# Library_v50.net
KiCad netlist of a schematic drawn in EAGLE
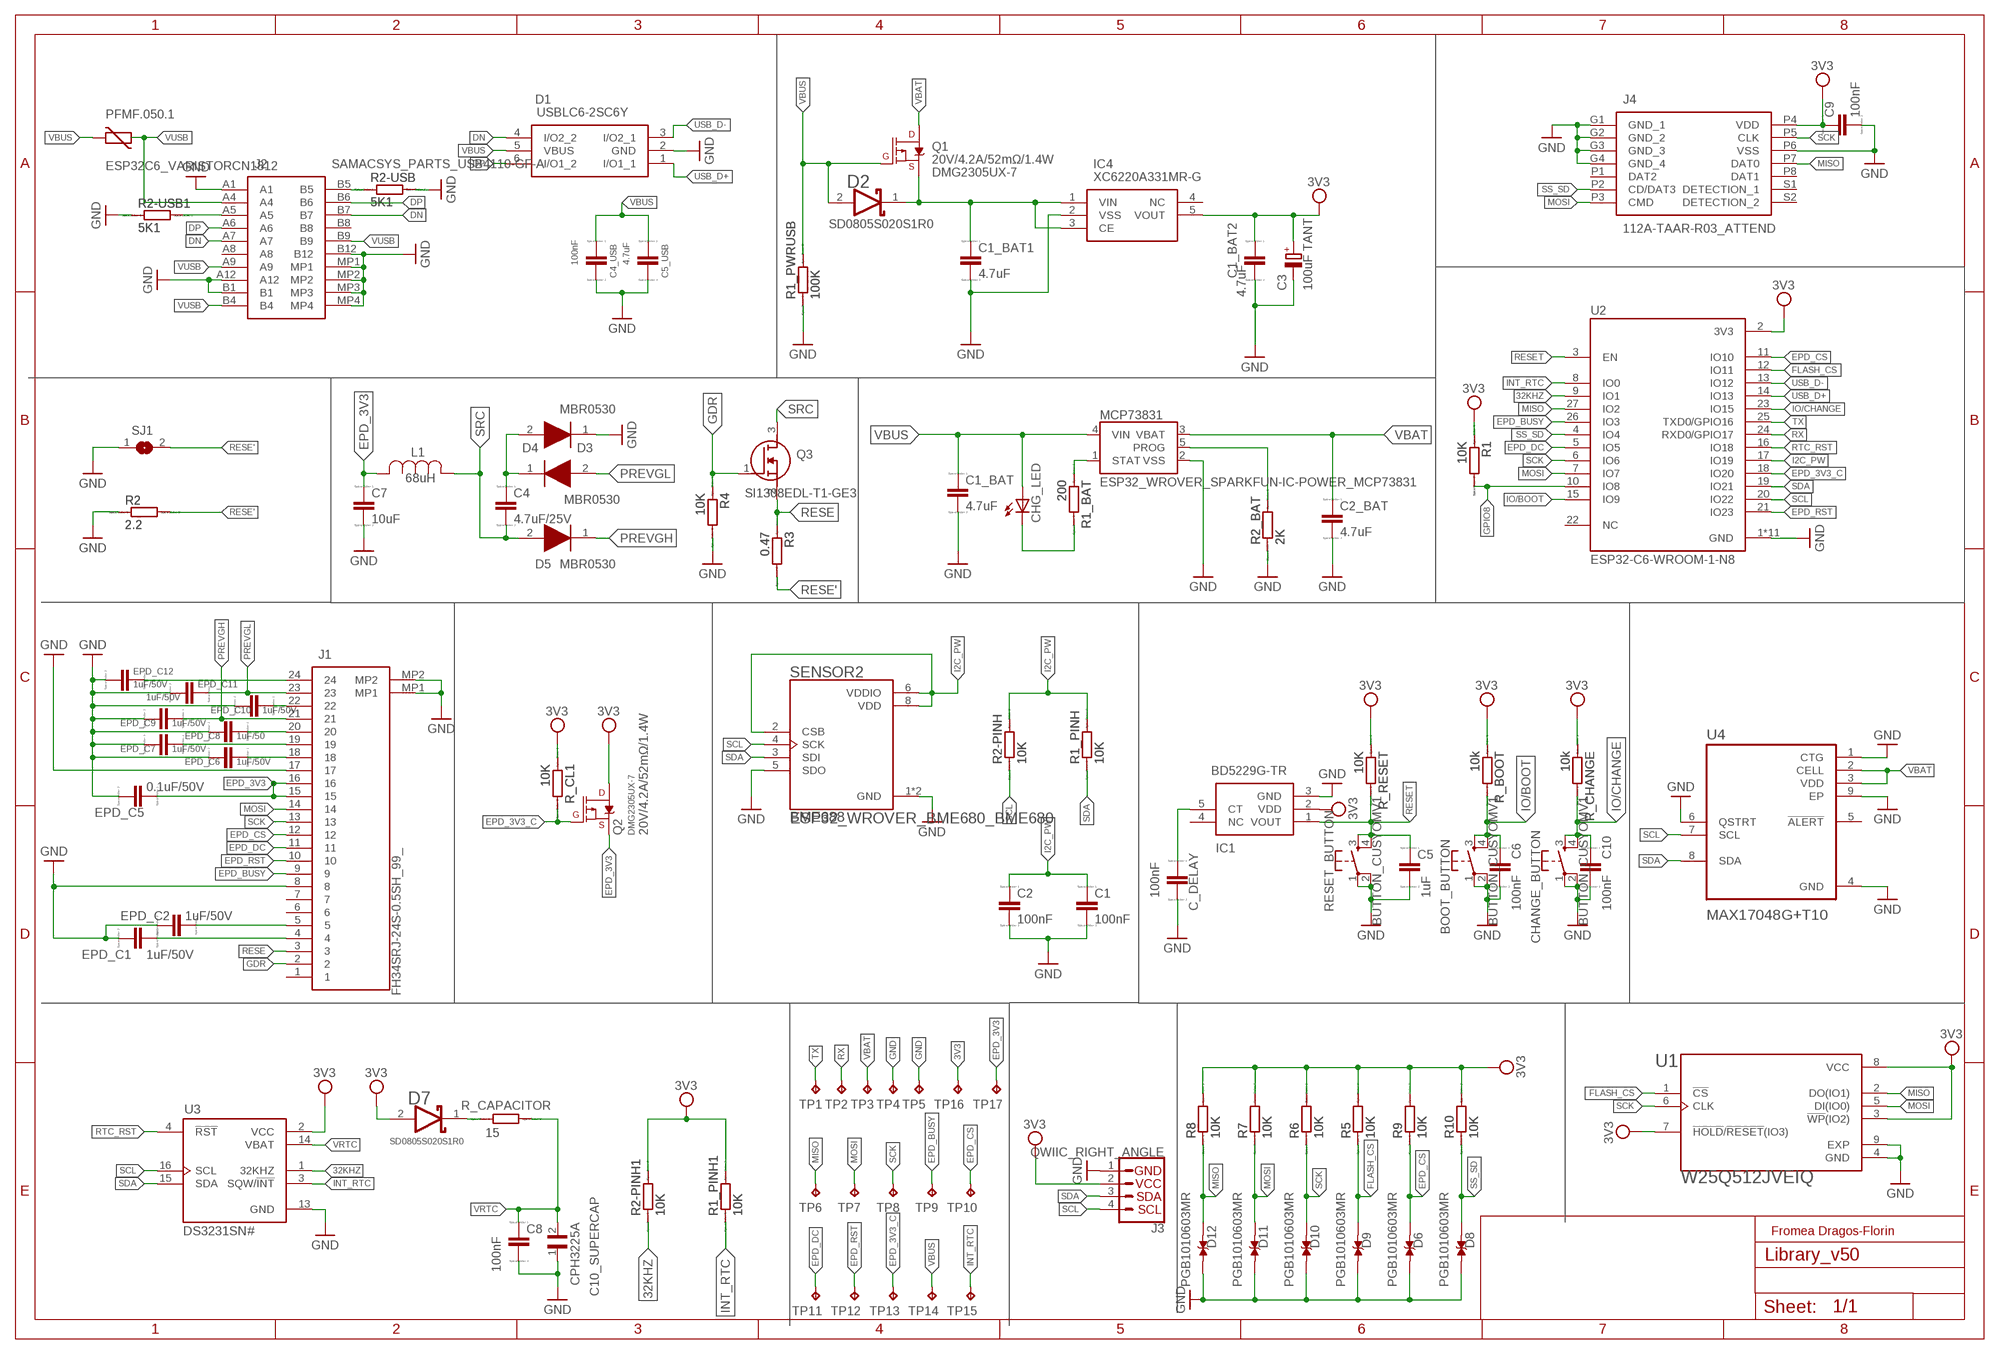
[diagram p0: schematic, sheet 1]

(export (version "E")
  (design (tool "Eeschema 10.0.6"))
  (components
    (comp (ref "BOOT_BUTTON")
      (value "BUTTON_CUSYOMV1")
      (footprint "eagle-import:MYBUTTON")
      (libsource (lib "eagle-import") (part "BUTTON_CUSYOMV1"))
    )
    (comp (ref "C1")
      (value "100nF")
      (footprint "eagle-import:ESP32_WROVER_EAGLE-LTSPICE_C0402")
      (libsource (lib "eagle-import") (part "ESP32_WROVER_EAGLE-LTSPICE_CC0402"))
    )
    (comp (ref "C1_BAT")
      (value "4.7uF")
      (footprint "eagle-import:ESP32_WROVER_EAGLE-LTSPICE_C0402")
      (libsource (lib "eagle-import") (part "ESP32_WROVER_EAGLE-LTSPICE_CC0402"))
    )
    (comp (ref "C1_BAT1")
      (value "4.7uF")
      (footprint "eagle-import:ESP32_WROVER_EAGLE-LTSPICE_C0402")
      (libsource (lib "eagle-import") (part "ESP32_WROVER_EAGLE-LTSPICE_CC0402"))
    )
    (comp (ref "C1_BAT2")
      (value "4.7uF")
      (footprint "eagle-import:ESP32_WROVER_EAGLE-LTSPICE_C0402")
      (libsource (lib "eagle-import") (part "ESP32_WROVER_EAGLE-LTSPICE_CC0402"))
    )
    (comp (ref "C2")
      (value "100nF")
      (footprint "eagle-import:ESP32_WROVER_EAGLE-LTSPICE_C0402")
      (libsource (lib "eagle-import") (part "ESP32_WROVER_EAGLE-LTSPICE_CC0402"))
    )
    (comp (ref "C2_BAT")
      (value "4.7uF")
      (footprint "eagle-import:ESP32_WROVER_EAGLE-LTSPICE_C0402")
      (libsource (lib "eagle-import") (part "ESP32_WROVER_EAGLE-LTSPICE_CC0402"))
    )
    (comp (ref "C3")
      (value "100uF TANT")
      (footprint "eagle-import:RCL_CT3528")
      (libsource (lib "eagle-import") (part "RCL_CPOL-EUCT3528"))
    )
    (comp (ref "C4")
      (value "4.7uF/25V")
      (footprint "eagle-import:ESP32_WROVER_EAGLE-LTSPICE_C0402")
      (libsource (lib "eagle-import") (part "ESP32_WROVER_EAGLE-LTSPICE_CC0402"))
    )
    (comp (ref "C4_USB")
      (value "100nF")
      (footprint "eagle-import:ESP32_WROVER_EAGLE-LTSPICE_C0402")
      (libsource (lib "eagle-import") (part "ESP32_WROVER_EAGLE-LTSPICE_CC0402"))
    )
    (comp (ref "C5")
      (value "1uF")
      (footprint "eagle-import:ESP32_WROVER_EAGLE-LTSPICE_C0402")
      (libsource (lib "eagle-import") (part "ESP32_WROVER_EAGLE-LTSPICE_CC0402"))
    )
    (comp (ref "C5_USB")
      (value "4.7uF")
      (footprint "eagle-import:ESP32_WROVER_EAGLE-LTSPICE_C0402")
      (libsource (lib "eagle-import") (part "ESP32_WROVER_EAGLE-LTSPICE_CC0402"))
    )
    (comp (ref "C6")
      (value "100nF")
      (footprint "eagle-import:ESP32_WROVER_EAGLE-LTSPICE_C0402")
      (libsource (lib "eagle-import") (part "ESP32_WROVER_EAGLE-LTSPICE_CC0402"))
    )
    (comp (ref "C7")
      (value "10uF")
      (footprint "eagle-import:ESP32_WROVER_EAGLE-LTSPICE_C0402")
      (libsource (lib "eagle-import") (part "ESP32_WROVER_EAGLE-LTSPICE_CC0402"))
    )
    (comp (ref "C8")
      (value "100nF")
      (footprint "eagle-import:ESP32_WROVER_EAGLE-LTSPICE_C0402")
      (libsource (lib "eagle-import") (part "ESP32_WROVER_EAGLE-LTSPICE_CC0402"))
    )
    (comp (ref "C9")
      (value "100nF")
      (footprint "eagle-import:ESP32_WROVER_EAGLE-LTSPICE_C0402")
      (libsource (lib "eagle-import") (part "ESP32_WROVER_EAGLE-LTSPICE_CC0402"))
    )
    (comp (ref "C10")
      (value "100nF")
      (footprint "eagle-import:ESP32_WROVER_EAGLE-LTSPICE_C0402")
      (libsource (lib "eagle-import") (part "ESP32_WROVER_EAGLE-LTSPICE_CC0402"))
    )
    (comp (ref "C10_SUPERCAP")
      (value "CPH3225A")
      (footprint "eagle-import:CAPCP3225X100N")
      (fields (field (name "MF") "Seiko Instruments"))
      (libsource (lib "eagle-import") (part "CPH3225A"))
    )
    (comp (ref "CHANGE_BUTTON")
      (value "BUTTON_CUSYOMV1")
      (footprint "eagle-import:MYBUTTON")
      (libsource (lib "eagle-import") (part "BUTTON_CUSYOMV1"))
    )
    (comp (ref "CHG_LED")
      (value "ADAFRUIT_LEDCHIP-LED0603")
      (footprint "eagle-import:ADAFRUIT_CHIP-LED0603")
      (libsource (lib "eagle-import") (part "ADAFRUIT_LEDCHIP-LED0603"))
    )
    (comp (ref "C_DELAY")
      (value "100nF")
      (footprint "eagle-import:ESP32_WROVER_EAGLE-LTSPICE_C0402")
      (libsource (lib "eagle-import") (part "ESP32_WROVER_EAGLE-LTSPICE_CC0402"))
    )
    (comp (ref "D1")
      (value "USBLC6-2SC6Y")
      (footprint "eagle-import:SOT95P280X145-6N")
      (fields (field (name "MF") "STMicroelectronics"))
      (libsource (lib "eagle-import") (part "USBLC6-2SC6Y"))
    )
    (comp (ref "D2")
      (value "ESP32_WROVER_AVX---SD0805S020S1R0_AVX_SD0805S020S1R0_0_0AVX_SD0805S020S1R0_0_0")
      (footprint "eagle-import:ESP32_WROVER_AVX---SD0805S020S1R0_AVX_SD0805S020S1R0_0")
      (fields
        (field (name "DIGIKEY_PART_NUMBER") "478-7800-1-ND")
        (field (name "MF") "AVX")
        (field (name "MOUSER_PART_NUMBER") "581-SD0805S020S1R0")
      )
      (libsource (lib "eagle-import") (part "ESP32_WROVER_AVX---SD0805S020S1R0_AVX_SD0805S020S1R0_0_0AVX_SD0805S020S1R0_0_0"))
    )
    (comp (ref "D3")
      (value "MBR0530")
      (footprint "eagle-import:SOD3716X135N")
      (fields (field (name "MF") "ON Semiconductor"))
      (libsource (lib "eagle-import") (part "MBR0530"))
    )
    (comp (ref "D4")
      (value "MBR0530")
      (footprint "eagle-import:SOD3716X135N")
      (fields (field (name "MF") "ON Semiconductor"))
      (libsource (lib "eagle-import") (part "MBR0530"))
    )
    (comp (ref "D5")
      (value "MBR0530")
      (footprint "eagle-import:SOD3716X135N")
      (fields (field (name "MF") "ON Semiconductor"))
      (libsource (lib "eagle-import") (part "MBR0530"))
    )
    (comp (ref "D6")
      (value "PGB1010603MR")
      (footprint "eagle-import:DIOC1608X36N")
      (fields (field (name "MF") "Littelfuse Inc."))
      (libsource (lib "eagle-import") (part "PGB1010603MR"))
    )
    (comp (ref "D7")
      (value "ESP32_WROVER_AVX---SD0805S020S1R0_AVX_SD0805S020S1R0_0_0AVX_SD0805S020S1R0_0_0")
      (footprint "eagle-import:ESP32_WROVER_AVX---SD0805S020S1R0_AVX_SD0805S020S1R0_0")
      (fields
        (field (name "DIGIKEY_PART_NUMBER") "478-7800-1-ND")
        (field (name "MF") "AVX")
        (field (name "MOUSER_PART_NUMBER") "581-SD0805S020S1R0")
      )
      (libsource (lib "eagle-import") (part "ESP32_WROVER_AVX---SD0805S020S1R0_AVX_SD0805S020S1R0_0_0AVX_SD0805S020S1R0_0_0"))
    )
    (comp (ref "D8")
      (value "PGB1010603MR")
      (footprint "eagle-import:DIOC1608X36N")
      (fields (field (name "MF") "Littelfuse Inc."))
      (libsource (lib "eagle-import") (part "PGB1010603MR"))
    )
    (comp (ref "D9")
      (value "PGB1010603MR")
      (footprint "eagle-import:DIOC1608X36N")
      (fields (field (name "MF") "Littelfuse Inc."))
      (libsource (lib "eagle-import") (part "PGB1010603MR"))
    )
    (comp (ref "D10")
      (value "PGB1010603MR")
      (footprint "eagle-import:DIOC1608X36N")
      (fields (field (name "MF") "Littelfuse Inc."))
      (libsource (lib "eagle-import") (part "PGB1010603MR"))
    )
    (comp (ref "D11")
      (value "PGB1010603MR")
      (footprint "eagle-import:DIOC1608X36N")
      (fields (field (name "MF") "Littelfuse Inc."))
      (libsource (lib "eagle-import") (part "PGB1010603MR"))
    )
    (comp (ref "D12")
      (value "PGB1010603MR")
      (footprint "eagle-import:DIOC1608X36N")
      (fields (field (name "MF") "Littelfuse Inc."))
      (libsource (lib "eagle-import") (part "PGB1010603MR"))
    )
    (comp (ref "EPD_C1")
      (value "1uF/50V")
      (footprint "eagle-import:ESP32_WROVER_EAGLE-LTSPICE_C0402")
      (libsource (lib "eagle-import") (part "ESP32_WROVER_EAGLE-LTSPICE_CC0402"))
    )
    (comp (ref "EPD_C2")
      (value "1uF/50V")
      (footprint "eagle-import:ESP32_WROVER_EAGLE-LTSPICE_C0402")
      (libsource (lib "eagle-import") (part "ESP32_WROVER_EAGLE-LTSPICE_CC0402"))
    )
    (comp (ref "EPD_C5")
      (value "0.1uF/50V")
      (footprint "eagle-import:ESP32_WROVER_EAGLE-LTSPICE_C0402")
      (libsource (lib "eagle-import") (part "ESP32_WROVER_EAGLE-LTSPICE_CC0402"))
    )
    (comp (ref "EPD_C6")
      (value "1uF/50V")
      (footprint "eagle-import:ESP32_WROVER_EAGLE-LTSPICE_C0402")
      (libsource (lib "eagle-import") (part "ESP32_WROVER_EAGLE-LTSPICE_CC0402"))
    )
    (comp (ref "EPD_C7")
      (value "1uF/50V")
      (footprint "eagle-import:ESP32_WROVER_EAGLE-LTSPICE_C0402")
      (libsource (lib "eagle-import") (part "ESP32_WROVER_EAGLE-LTSPICE_CC0402"))
    )
    (comp (ref "EPD_C8")
      (value "1uF/50")
      (footprint "eagle-import:ESP32_WROVER_EAGLE-LTSPICE_C0402")
      (libsource (lib "eagle-import") (part "ESP32_WROVER_EAGLE-LTSPICE_CC0402"))
    )
    (comp (ref "EPD_C9")
      (value "1uF/50V")
      (footprint "eagle-import:ESP32_WROVER_EAGLE-LTSPICE_C0402")
      (libsource (lib "eagle-import") (part "ESP32_WROVER_EAGLE-LTSPICE_CC0402"))
    )
    (comp (ref "EPD_C10")
      (value "1uF/50V")
      (footprint "eagle-import:ESP32_WROVER_EAGLE-LTSPICE_C0402")
      (libsource (lib "eagle-import") (part "ESP32_WROVER_EAGLE-LTSPICE_CC0402"))
    )
    (comp (ref "EPD_C11")
      (value "1uF/50V")
      (footprint "eagle-import:ESP32_WROVER_EAGLE-LTSPICE_C0402")
      (libsource (lib "eagle-import") (part "ESP32_WROVER_EAGLE-LTSPICE_CC0402"))
    )
    (comp (ref "EPD_C12")
      (value "1uF/50V")
      (footprint "eagle-import:ESP32_WROVER_EAGLE-LTSPICE_C0402")
      (libsource (lib "eagle-import") (part "ESP32_WROVER_EAGLE-LTSPICE_CC0402"))
    )
    (comp (ref "IC1")
      (value "BD5229G-TR")
      (footprint "eagle-import:SOT95P280X125-5N")
      (fields (field (name "MOUSER_PART_NUMBER") "755-BD5229G-TR"))
      (libsource (lib "eagle-import") (part "BD5229G-TR"))
    )
    (comp (ref "IC4")
      (value "XC6220A331MR-G")
      (footprint "eagle-import:SOT95P280X120-5N")
      (fields (field (name "MOUSER_PART_NUMBER") "865-XC6220A331MR-G"))
      (libsource (lib "eagle-import") (part "XC6220A331MR-G"))
    )
    (comp (ref "J1")
      (value "FH34SRJ-24S-0.5SH_99_")
      (footprint "eagle-import:FH34SRJ24S05SH99")
      (fields
        (field (name "MANUFACTURER_PART_NUMBER") "FH34SRJ-24S-0.5SH(99)")
        (field (name "MOUSER_PART_NUMBER") "798-FH34SRJ24S05SH99")
      )
      (libsource (lib "eagle-import") (part "FH34SRJ-24S-0.5SH_99_"))
    )
    (comp (ref "J2")
      (value "SAMACSYS_PARTS_USB4110-GF-A")
      (footprint "eagle-import:SAMACSYS_PARTS_USB4110GFA")
      (fields
        (field (name "MANUFACTURER_PART_NUMBER") "USB4110-GF-A")
        (field (name "MOUSER_PART_NUMBER") "640-USB4110-GF-A")
      )
      (libsource (lib "eagle-import") (part "SAMACSYS_PARTS_USB4110-GF-A"))
    )
    (comp (ref "J3")
      (value "QWIIC_RIGHT_ANGLE")
      (footprint "eagle-import:JST04_1MM_RA")
      (libsource (lib "eagle-import") (part "QWIIC_CONNECTORJS-1MM"))
    )
    (comp (ref "J4")
      (value "112A-TAAR-R03_ATTEND")
      (footprint "eagle-import:112ATAARR03ATTEND")
      (fields (field (name "MANUFACTURER_PART_NUMBER") "112A-TAAR-R03 ATTEND"))
      (libsource (lib "eagle-import") (part "112A-TAAR-R03_ATTEND"))
    )
    (comp (ref "L1")
      (value "68uH")
      (footprint "eagle-import:IND_4828-WE-TPC_WRE")
      (fields
        (field (name "MANUFACTURER_PART_NUMBER") "744043680")
        (field (name "COPYRIGHT") "Copyright (C) 2024 Ultra Librarian. All rights reserved.")
      )
      (libsource (lib "eagle-import") (part "744043680IND_4828-WE-TPC_WRE"))
    )
    (comp (ref "MCP73831")
      (value "ESP32_WROVER_SPARKFUN-IC-POWER_MCP73831")
      (footprint "eagle-import:ESP32_WROVER_SPARKFUN-IC-POWER_SOT23-5")
      (libsource (lib "eagle-import") (part "ESP32_WROVER_SPARKFUN-IC-POWER_MCP73831"))
    )
    (comp (ref "PFMF.050.1")
      (value "ESP32C6_VARISTORCN1812")
      (footprint "eagle-import:ESP32C6_VARISTOR_CT_CN1812")
      (libsource (lib "eagle-import") (part "ESP32C6_VARISTORCN1812"))
    )
    (comp (ref "Q1")
      (value "20V/4.2A/52mΩ/1.4W")
      (footprint "eagle-import:ESP32_WROVER_SPARKFUN-DISCRETESEMI_SOT23-3")
      (libsource (lib "eagle-import") (part "ESP32_WROVER_SPARKFUN-DISCRETESEMI_MOSFET_PCH-DMG2305UX-7"))
    )
    (comp (ref "Q2")
      (value "20V/4.2A/52mΩ/1.4W")
      (footprint "eagle-import:ESP32_WROVER_SPARKFUN-DISCRETESEMI_SOT23-3")
      (libsource (lib "eagle-import") (part "ESP32_WROVER_SPARKFUN-DISCRETESEMI_MOSFET_PCH-DMG2305UX-7"))
    )
    (comp (ref "Q3")
      (value "SI1308EDL-T1-GE3")
      (footprint "eagle-import:SOT65P210X110-3N")
      (fields (field (name "MF") "Vishay Siliconix"))
      (libsource (lib "eagle-import") (part "SI1308EDL-T1-GE3"))
    )
    (comp (ref "R1")
      (value "10K")
      (footprint "eagle-import:ESP32_WROVER_EAGLE-LTSPICE_R0402")
      (libsource (lib "eagle-import") (part "ESP32_WROVER_EAGLE-LTSPICE_RR0402"))
    )
    (comp (ref "R1_BAT")
      (value "200")
      (footprint "eagle-import:ESP32_WROVER_EAGLE-LTSPICE_R0402")
      (libsource (lib "eagle-import") (part "ESP32_WROVER_EAGLE-LTSPICE_RR0402"))
    )
    (comp (ref "R1_PINH")
      (value "10K")
      (footprint "eagle-import:ESP32_WROVER_EAGLE-LTSPICE_R0402")
      (libsource (lib "eagle-import") (part "ESP32_WROVER_EAGLE-LTSPICE_RR0402"))
    )
    (comp (ref "R1_PINH1")
      (value "10K")
      (footprint "eagle-import:ESP32_WROVER_EAGLE-LTSPICE_R0402")
      (libsource (lib "eagle-import") (part "ESP32_WROVER_EAGLE-LTSPICE_RR0402"))
    )
    (comp (ref "R1_PWRUSB")
      (value "100K")
      (footprint "eagle-import:ESP32_WROVER_EAGLE-LTSPICE_R0402")
      (libsource (lib "eagle-import") (part "ESP32_WROVER_EAGLE-LTSPICE_RR0402"))
    )
    (comp (ref "R2")
      (value "2.2")
      (footprint "eagle-import:ESP32_WROVER_EAGLE-LTSPICE_R0402")
      (libsource (lib "eagle-import") (part "ESP32_WROVER_EAGLE-LTSPICE_RR0402"))
    )
    (comp (ref "R2-PINH")
      (value "10K")
      (footprint "eagle-import:ESP32_WROVER_EAGLE-LTSPICE_R0402")
      (libsource (lib "eagle-import") (part "ESP32_WROVER_EAGLE-LTSPICE_RR0402"))
    )
    (comp (ref "R2-PINH1")
      (value "10K")
      (footprint "eagle-import:ESP32_WROVER_EAGLE-LTSPICE_R0402")
      (libsource (lib "eagle-import") (part "ESP32_WROVER_EAGLE-LTSPICE_RR0402"))
    )
    (comp (ref "R2-USB")
      (value "5K1")
      (footprint "eagle-import:ESP32_WROVER_EAGLE-LTSPICE_R0402")
      (libsource (lib "eagle-import") (part "ESP32_WROVER_EAGLE-LTSPICE_RR0402"))
    )
    (comp (ref "R2-USB1")
      (value "5K1")
      (footprint "eagle-import:ESP32_WROVER_EAGLE-LTSPICE_R0402")
      (libsource (lib "eagle-import") (part "ESP32_WROVER_EAGLE-LTSPICE_RR0402"))
    )
    (comp (ref "R2_BAT")
      (value "2K")
      (footprint "eagle-import:ESP32_WROVER_EAGLE-LTSPICE_R0402")
      (libsource (lib "eagle-import") (part "ESP32_WROVER_EAGLE-LTSPICE_RR0402"))
    )
    (comp (ref "R3")
      (value "0.47")
      (footprint "eagle-import:ESP32_WROVER_EAGLE-LTSPICE_R0402")
      (libsource (lib "eagle-import") (part "ESP32_WROVER_EAGLE-LTSPICE_RR0402"))
    )
    (comp (ref "R4")
      (value "10K")
      (footprint "eagle-import:ESP32_WROVER_EAGLE-LTSPICE_R0402")
      (libsource (lib "eagle-import") (part "ESP32_WROVER_EAGLE-LTSPICE_RR0402"))
    )
    (comp (ref "R5")
      (value "10K")
      (footprint "eagle-import:ESP32_WROVER_EAGLE-LTSPICE_R0402")
      (libsource (lib "eagle-import") (part "ESP32_WROVER_EAGLE-LTSPICE_RR0402"))
    )
    (comp (ref "R6")
      (value "10K")
      (footprint "eagle-import:ESP32_WROVER_EAGLE-LTSPICE_R0402")
      (libsource (lib "eagle-import") (part "ESP32_WROVER_EAGLE-LTSPICE_RR0402"))
    )
    (comp (ref "R7")
      (value "10K")
      (footprint "eagle-import:ESP32_WROVER_EAGLE-LTSPICE_R0402")
      (libsource (lib "eagle-import") (part "ESP32_WROVER_EAGLE-LTSPICE_RR0402"))
    )
    (comp (ref "R8")
      (value "10K")
      (footprint "eagle-import:ESP32_WROVER_EAGLE-LTSPICE_R0402")
      (libsource (lib "eagle-import") (part "ESP32_WROVER_EAGLE-LTSPICE_RR0402"))
    )
    (comp (ref "R9")
      (value "10K")
      (footprint "eagle-import:ESP32_WROVER_EAGLE-LTSPICE_R0402")
      (libsource (lib "eagle-import") (part "ESP32_WROVER_EAGLE-LTSPICE_RR0402"))
    )
    (comp (ref "R10")
      (value "10K")
      (footprint "eagle-import:ESP32_WROVER_EAGLE-LTSPICE_R0402")
      (libsource (lib "eagle-import") (part "ESP32_WROVER_EAGLE-LTSPICE_RR0402"))
    )
    (comp (ref "RESET_BUTTON")
      (value "BUTTON_CUSYOMV1")
      (footprint "eagle-import:MYBUTTON")
      (libsource (lib "eagle-import") (part "BUTTON_CUSYOMV1"))
    )
    (comp (ref "R_BOOT")
      (value "10k")
      (footprint "eagle-import:ESP32_WROVER_EAGLE-LTSPICE_R0402")
      (libsource (lib "eagle-import") (part "ESP32_WROVER_EAGLE-LTSPICE_RR0402"))
    )
    (comp (ref "R_CAPACITOR")
      (value "15")
      (footprint "eagle-import:ESP32_WROVER_EAGLE-LTSPICE_R0402")
      (libsource (lib "eagle-import") (part "ESP32_WROVER_EAGLE-LTSPICE_RR0402"))
    )
    (comp (ref "R_CHANGE")
      (value "10k")
      (footprint "eagle-import:ESP32_WROVER_EAGLE-LTSPICE_R0402")
      (libsource (lib "eagle-import") (part "ESP32_WROVER_EAGLE-LTSPICE_RR0402"))
    )
    (comp (ref "R_CL1")
      (value "10K")
      (footprint "eagle-import:ESP32_WROVER_EAGLE-LTSPICE_R0402")
      (libsource (lib "eagle-import") (part "ESP32_WROVER_EAGLE-LTSPICE_RR0402"))
    )
    (comp (ref "R_RESET")
      (value "10K")
      (footprint "eagle-import:ESP32_WROVER_EAGLE-LTSPICE_R0402")
      (libsource (lib "eagle-import") (part "ESP32_WROVER_EAGLE-LTSPICE_RR0402"))
    )
    (comp (ref "SENSOR2")
      (value "ESP32_WROVER_BME680_BME680")
      (footprint "eagle-import:ESP32_WROVER_BME680_PSON80P300X300X100-8N")
      (fields (field (name "MF") "Bosch Sensortec") (field (name "MP") "BME680"))
      (libsource (lib "eagle-import") (part "ESP32_WROVER_BME680_BME680"))
    )
    (comp (ref "SJ1") (value "SJ") (footprint "eagle-import:SJ") (libsource (lib "eagle-import") (part "SJ")))
    (comp (ref "TP1")
      (value "TPTP20R")
      (footprint "eagle-import:TP20R")
      (libsource (lib "eagle-import") (part "TPTP20R"))
    )
    (comp (ref "TP2")
      (value "TPTP20R")
      (footprint "eagle-import:TP20R")
      (libsource (lib "eagle-import") (part "TPTP20R"))
    )
    (comp (ref "TP3")
      (value "TPTP20R")
      (footprint "eagle-import:TP20R")
      (libsource (lib "eagle-import") (part "TPTP20R"))
    )
    (comp (ref "TP4")
      (value "TPTP20R")
      (footprint "eagle-import:TP20R")
      (libsource (lib "eagle-import") (part "TPTP20R"))
    )
    (comp (ref "TP5")
      (value "TPTP20R")
      (footprint "eagle-import:TP20R")
      (libsource (lib "eagle-import") (part "TPTP20R"))
    )
    (comp (ref "TP6")
      (value "TPTP20R")
      (footprint "eagle-import:TP20R")
      (libsource (lib "eagle-import") (part "TPTP20R"))
    )
    (comp (ref "TP7")
      (value "TPTP20R")
      (footprint "eagle-import:TP20R")
      (libsource (lib "eagle-import") (part "TPTP20R"))
    )
    (comp (ref "TP8")
      (value "TPTP20R")
      (footprint "eagle-import:TP20R")
      (libsource (lib "eagle-import") (part "TPTP20R"))
    )
    (comp (ref "TP9")
      (value "TPTP20R")
      (footprint "eagle-import:TP20R")
      (libsource (lib "eagle-import") (part "TPTP20R"))
    )
    (comp (ref "TP10")
      (value "TPTP20R")
      (footprint "eagle-import:TP20R")
      (libsource (lib "eagle-import") (part "TPTP20R"))
    )
    (comp (ref "TP11")
      (value "TPTP20R")
      (footprint "eagle-import:TP20R")
      (libsource (lib "eagle-import") (part "TPTP20R"))
    )
    (comp (ref "TP12")
      (value "TPTP20R")
      (footprint "eagle-import:TP20R")
      (libsource (lib "eagle-import") (part "TPTP20R"))
    )
    (comp (ref "TP13")
      (value "TPTP20R")
      (footprint "eagle-import:TP20R")
      (libsource (lib "eagle-import") (part "TPTP20R"))
    )
    (comp (ref "TP14")
      (value "TPTP20R")
      (footprint "eagle-import:TP20R")
      (libsource (lib "eagle-import") (part "TPTP20R"))
    )
    (comp (ref "TP15")
      (value "TPTP20R")
      (footprint "eagle-import:TP20R")
      (libsource (lib "eagle-import") (part "TPTP20R"))
    )
    (comp (ref "TP16")
      (value "TPTP20R")
      (footprint "eagle-import:TP20R")
      (libsource (lib "eagle-import") (part "TPTP20R"))
    )
    (comp (ref "TP17")
      (value "TPTP20R")
      (footprint "eagle-import:TP20R")
      (libsource (lib "eagle-import") (part "TPTP20R"))
    )
    (comp (ref "U1")
      (value "W25Q512JVEIQ")
      (footprint "eagle-import:SON127P600X800X80-9N")
      (fields (field (name "MF") "Winbond Electronics"))
      (libsource (lib "eagle-import") (part "W25Q512JVEIQ"))
    )
    (comp (ref "U2")
      (value "ESP32-C6-WROOM-1-N8")
      (footprint "eagle-import:XCVR_ESP32-C6-WROOM-1-N8")
      (fields (field (name "MF") "Espressif Systems"))
      (libsource (lib "eagle-import") (part "ESP32-C6-WROOM-1-N8"))
    )
    (comp (ref "U3")
      (value "DS3231SN#")
      (footprint "eagle-import:SOIC127P1032X265-16N")
      (fields (field (name "MF") "Analog Devices"))
      (libsource (lib "eagle-import") (part "DS3231SN#"))
    )
    (comp (ref "U4")
      (value "MAX17048G+T10")
      (footprint "eagle-import:SON50P200X200X80-9N")
      (fields (field (name "MF") "Analog Devices"))
      (libsource (lib "eagle-import") (part "MAX17048G+T10"))
    )
  )
  (nets
    (net (code "1") (name "3V3") (class "Default")
      (node (ref "C1_BAT2") (pin "1") (pinfunction "1_1") (pintype "passive"))
      (node (ref "C3") (pin "+") (pinfunction "+_+") (pintype "passive"))
      (node (ref "C9") (pin "1") (pinfunction "1_1") (pintype "passive"))
      (node (ref "D7") (pin "2") (pinfunction "ANODE_2") (pintype "bidirectional"))
      (node (ref "IC1") (pin "2") (pinfunction "VDD_2") (pintype "bidirectional"))
      (node (ref "IC4") (pin "5") (pinfunction "VOUT_5") (pintype "bidirectional"))
      (node (ref "J3") (pin "2") (pinfunction "2_2") (pintype "power_in"))
      (node (ref "J4") (pin "P4") (pinfunction "VDD_P4") (pintype "bidirectional"))
      (node (ref "Q2") (pin "3") (pinfunction "D_3") (pintype "bidirectional"))
      (node (ref "R1") (pin "1") (pinfunction "1_1") (pintype "passive"))
      (node (ref "R10") (pin "2") (pinfunction "2_2") (pintype "passive"))
      (node (ref "R1_PINH1") (pin "2") (pinfunction "2_2") (pintype "passive"))
      (node (ref "R2-PINH1") (pin "2") (pinfunction "2_2") (pintype "passive"))
      (node (ref "R5") (pin "2") (pinfunction "2_2") (pintype "passive"))
      (node (ref "R6") (pin "2") (pinfunction "2_2") (pintype "passive"))
      (node (ref "R7") (pin "2") (pinfunction "2_2") (pintype "passive"))
      (node (ref "R8") (pin "2") (pinfunction "2_2") (pintype "passive"))
      (node (ref "R9") (pin "2") (pinfunction "2_2") (pintype "passive"))
      (node (ref "R_BOOT") (pin "1") (pinfunction "1_1") (pintype "passive"))
      (node (ref "R_CHANGE") (pin "1") (pinfunction "1_1") (pintype "passive"))
      (node (ref "R_CL1") (pin "1") (pinfunction "1_1") (pintype "passive"))
      (node (ref "R_RESET") (pin "1") (pinfunction "1_1") (pintype "passive"))
      (node (ref "TP16") (pin "TP") (pinfunction "TP_TP") (pintype "input"))
      (node (ref "U1") (pin "3") (pinfunction "~{WP}(IO2)_3") (pintype "bidirectional"))
      (node (ref "U1") (pin "7") (pinfunction "~{HOLD}/~{RESET}(IO3)_7") (pintype "bidirectional"))
      (node (ref "U1") (pin "8") (pinfunction "VCC_8") (pintype "power_in"))
      (node (ref "U2") (pin "2") (pinfunction "3V3_2") (pintype "power_in"))
      (node (ref "U3") (pin "2") (pinfunction "VCC_2") (pintype "power_in"))
    )
    (net (code "2") (name "32KHZ") (class "Default")
      (node (ref "R2-PINH1") (pin "1") (pinfunction "1_1") (pintype "passive"))
      (node (ref "U2") (pin "9") (pinfunction "IO1_9") (pintype "bidirectional"))
      (node (ref "U3") (pin "1") (pinfunction "32KHZ_1") (pintype "output"))
    )
    (net (code "3") (name "DN") (class "Default")
      (node (ref "D1") (pin "4") (pinfunction "I/O2_2_4") (pintype "bidirectional"))
      (node (ref "J2") (pin "A7") (pinfunction "A7_A7") (pintype "bidirectional"))
      (node (ref "J2") (pin "B7") (pinfunction "B7_B7") (pintype "bidirectional"))
    )
    (net (code "4") (name "DP") (class "Default")
      (node (ref "D1") (pin "6") (pinfunction "I/O1_2_6") (pintype "bidirectional"))
      (node (ref "J2") (pin "A6") (pinfunction "A6_A6") (pintype "bidirectional"))
      (node (ref "J2") (pin "B6") (pinfunction "B6_B6") (pintype "bidirectional"))
    )
    (net (code "5") (name "EPD_3V3") (class "Default")
      (node (ref "C7") (pin "1") (pinfunction "1_1") (pintype "passive"))
      (node (ref "EPD_C5") (pin "1") (pinfunction "1_1") (pintype "passive"))
      (node (ref "J1") (pin "15") (pinfunction "15_15") (pintype "bidirectional"))
      (node (ref "J1") (pin "16") (pinfunction "16_16") (pintype "bidirectional"))
      (node (ref "L1") (pin "2") (pinfunction "2_2") (pintype "passive"))
      (node (ref "Q2") (pin "2") (pinfunction "S_2") (pintype "bidirectional"))
      (node (ref "TP17") (pin "TP") (pinfunction "TP_TP") (pintype "input"))
    )
    (net (code "6") (name "EPD_3V3_C") (class "Default")
      (node (ref "Q2") (pin "1") (pinfunction "G_1") (pintype "bidirectional"))
      (node (ref "R_CL1") (pin "2") (pinfunction "2_2") (pintype "passive"))
      (node (ref "TP13") (pin "TP") (pinfunction "TP_TP") (pintype "input"))
      (node (ref "U2") (pin "18") (pinfunction "IO20_18") (pintype "bidirectional"))
    )
    (net (code "7") (name "EPD_BUSY") (class "Default")
      (node (ref "J1") (pin "9") (pinfunction "9_9") (pintype "bidirectional"))
      (node (ref "TP9") (pin "TP") (pinfunction "TP_TP") (pintype "input"))
      (node (ref "U2") (pin "26") (pinfunction "IO3_26") (pintype "bidirectional"))
    )
    (net (code "8") (name "EPD_CS") (class "Default")
      (node (ref "D6") (pin "2") (pinfunction "2_2") (pintype "passive"))
      (node (ref "J1") (pin "12") (pinfunction "12_12") (pintype "bidirectional"))
      (node (ref "R9") (pin "1") (pinfunction "1_1") (pintype "passive"))
      (node (ref "TP10") (pin "TP") (pinfunction "TP_TP") (pintype "input"))
      (node (ref "U2") (pin "11") (pinfunction "IO10_11") (pintype "bidirectional"))
    )
    (net (code "9") (name "EPD_DC") (class "Default")
      (node (ref "J1") (pin "11") (pinfunction "11_11") (pintype "bidirectional"))
      (node (ref "TP11") (pin "TP") (pinfunction "TP_TP") (pintype "input"))
      (node (ref "U2") (pin "5") (pinfunction "IO5_5") (pintype "bidirectional"))
    )
    (net (code "10") (name "EPD_RST") (class "Default")
      (node (ref "J1") (pin "10") (pinfunction "10_10") (pintype "bidirectional"))
      (node (ref "TP12") (pin "TP") (pinfunction "TP_TP") (pintype "input"))
      (node (ref "U2") (pin "21") (pinfunction "IO23_21") (pintype "bidirectional"))
    )
    (net (code "11") (name "FLASH_CS") (class "Default")
      (node (ref "D9") (pin "2") (pinfunction "2_2") (pintype "passive"))
      (node (ref "R5") (pin "1") (pinfunction "1_1") (pintype "passive"))
      (node (ref "U1") (pin "1") (pinfunction "~{CS}_1") (pintype "input"))
      (node (ref "U2") (pin "12") (pinfunction "IO11_12") (pintype "bidirectional"))
    )
    (net (code "12") (name "GDR") (class "Default")
      (node (ref "J1") (pin "2") (pinfunction "2_2") (pintype "bidirectional"))
      (node (ref "Q3") (pin "1") (pinfunction "G_1") (pintype "bidirectional"))
      (node (ref "R4") (pin "1") (pinfunction "1_1") (pintype "passive"))
    )
    (net (code "13") (name "GND") (class "Default")
      (node (ref "BOOT_BUTTON") (pin "1") (pinfunction "1_1") (pintype "passive"))
      (node (ref "BOOT_BUTTON") (pin "2") (pinfunction "2_2") (pintype "passive"))
      (node (ref "C1") (pin "2") (pinfunction "2_2") (pintype "passive"))
      (node (ref "C10") (pin "2") (pinfunction "2_2") (pintype "passive"))
      (node (ref "C10_SUPERCAP") (pin "1") (pinfunction "1_1") (pintype "passive"))
      (node (ref "C1_BAT") (pin "2") (pinfunction "2_2") (pintype "passive"))
      (node (ref "C1_BAT1") (pin "2") (pinfunction "2_2") (pintype "passive"))
      (node (ref "C1_BAT2") (pin "2") (pinfunction "2_2") (pintype "passive"))
      (node (ref "C2") (pin "2") (pinfunction "2_2") (pintype "passive"))
      (node (ref "C2_BAT") (pin "2") (pinfunction "2_2") (pintype "passive"))
      (node (ref "C3") (pin "-") (pinfunction "-_-") (pintype "passive"))
      (node (ref "C4_USB") (pin "2") (pinfunction "2_2") (pintype "passive"))
      (node (ref "C5") (pin "2") (pinfunction "2_2") (pintype "passive"))
      (node (ref "C5_USB") (pin "2") (pinfunction "2_2") (pintype "passive"))
      (node (ref "C6") (pin "2") (pinfunction "2_2") (pintype "passive"))
      (node (ref "C7") (pin "2") (pinfunction "2_2") (pintype "passive"))
      (node (ref "C8") (pin "2") (pinfunction "2_2") (pintype "passive"))
      (node (ref "C9") (pin "2") (pinfunction "2_2") (pintype "passive"))
      (node (ref "CHANGE_BUTTON") (pin "1") (pinfunction "1_1") (pintype "passive"))
      (node (ref "CHANGE_BUTTON") (pin "2") (pinfunction "2_2") (pintype "passive"))
      (node (ref "C_DELAY") (pin "2") (pinfunction "2_2") (pintype "passive"))
      (node (ref "D1") (pin "2") (pinfunction "GND_2") (pintype "bidirectional"))
      (node (ref "D10") (pin "1") (pinfunction "1_1") (pintype "passive"))
      (node (ref "D11") (pin "1") (pinfunction "1_1") (pintype "passive"))
      (node (ref "D12") (pin "1") (pinfunction "1_1") (pintype "passive"))
      (node (ref "D4") (pin "1") (pinfunction "K_1") (pintype "bidirectional"))
      (node (ref "D6") (pin "1") (pinfunction "1_1") (pintype "passive"))
      (node (ref "D8") (pin "1") (pinfunction "1_1") (pintype "passive"))
      (node (ref "D9") (pin "1") (pinfunction "1_1") (pintype "passive"))
      (node (ref "EPD_C1") (pin "2") (pinfunction "2_2") (pintype "passive"))
      (node (ref "EPD_C10") (pin "2") (pinfunction "2_2") (pintype "passive"))
      (node (ref "EPD_C11") (pin "2") (pinfunction "2_2") (pintype "passive"))
      (node (ref "EPD_C12") (pin "2") (pinfunction "2_2") (pintype "passive"))
      (node (ref "EPD_C2") (pin "2") (pinfunction "2_2") (pintype "passive"))
      (node (ref "EPD_C5") (pin "2") (pinfunction "2_2") (pintype "passive"))
      (node (ref "EPD_C6") (pin "2") (pinfunction "2_2") (pintype "passive"))
      (node (ref "EPD_C7") (pin "2") (pinfunction "2_2") (pintype "passive"))
      (node (ref "EPD_C8") (pin "2") (pinfunction "2_2") (pintype "passive"))
      (node (ref "EPD_C9") (pin "2") (pinfunction "2_2") (pintype "passive"))
      (node (ref "IC1") (pin "3") (pinfunction "GND_3") (pintype "bidirectional"))
      (node (ref "IC4") (pin "2") (pinfunction "VSS_2") (pintype "bidirectional"))
      (node (ref "J1") (pin "17") (pinfunction "17_17") (pintype "bidirectional"))
      (node (ref "J1") (pin "8") (pinfunction "8_8") (pintype "bidirectional"))
      (node (ref "J1") (pin "MP1") (pinfunction "MP1_MP1") (pintype "bidirectional"))
      (node (ref "J1") (pin "MP2") (pinfunction "MP2_MP2") (pintype "bidirectional"))
      (node (ref "J2") (pin "A1") (pinfunction "A1_A1") (pintype "bidirectional"))
      (node (ref "J2") (pin "A12") (pinfunction "A12_A12") (pintype "bidirectional"))
      (node (ref "J2") (pin "B1") (pinfunction "B1_B1") (pintype "bidirectional"))
      (node (ref "J2") (pin "B12") (pinfunction "B12_B12") (pintype "bidirectional"))
      (node (ref "J2") (pin "MP1") (pinfunction "MP1_MP1") (pintype "bidirectional"))
      (node (ref "J2") (pin "MP2") (pinfunction "MP2_MP2") (pintype "bidirectional"))
      (node (ref "J2") (pin "MP3") (pinfunction "MP3_MP3") (pintype "bidirectional"))
      (node (ref "J2") (pin "MP4") (pinfunction "MP4_MP4") (pintype "bidirectional"))
      (node (ref "J3") (pin "1") (pinfunction "1_1") (pintype "power_in"))
      (node (ref "J4") (pin "G1") (pinfunction "GND_1_G1") (pintype "bidirectional"))
      (node (ref "J4") (pin "G2") (pinfunction "GND_2_G2") (pintype "bidirectional"))
      (node (ref "J4") (pin "G3") (pinfunction "GND_3_G3") (pintype "bidirectional"))
      (node (ref "J4") (pin "G4") (pinfunction "GND_4_G4") (pintype "bidirectional"))
      (node (ref "J4") (pin "P6") (pinfunction "VSS_P6") (pintype "bidirectional"))
      (node (ref "MCP73831") (pin "2") (pinfunction "VSS_2") (pintype "power_in"))
      (node (ref "R1_PWRUSB") (pin "1") (pinfunction "1_1") (pintype "passive"))
      (node (ref "R2") (pin "1") (pinfunction "1_1") (pintype "passive"))
      (node (ref "R2-USB") (pin "2") (pinfunction "2_2") (pintype "passive"))
      (node (ref "R2-USB1") (pin "1") (pinfunction "1_1") (pintype "passive"))
      (node (ref "R2_BAT") (pin "1") (pinfunction "1_1") (pintype "passive"))
      (node (ref "R4") (pin "2") (pinfunction "2_2") (pintype "passive"))
      (node (ref "RESET_BUTTON") (pin "1") (pinfunction "1_1") (pintype "passive"))
      (node (ref "RESET_BUTTON") (pin "2") (pinfunction "2_2") (pintype "passive"))
      (node (ref "SENSOR2") (pin "1") (pinfunction "GND_1") (pintype "power_in"))
      (node (ref "SENSOR2") (pin "5") (pinfunction "SDO_5") (pintype "bidirectional"))
      (node (ref "SENSOR2") (pin "7") (pinfunction "GND_7") (pintype "power_in"))
      (node (ref "SJ1") (pin "1") (pinfunction "1_1") (pintype "passive"))
      (node (ref "TP4") (pin "TP") (pinfunction "TP_TP") (pintype "input"))
      (node (ref "TP5") (pin "TP") (pinfunction "TP_TP") (pintype "input"))
      (node (ref "U1") (pin "4") (pinfunction "GND_4") (pintype "power_in"))
      (node (ref "U1") (pin "9") (pinfunction "EXP_9") (pintype "passive"))
      (node (ref "U2") (pin "1") (pinfunction "GND_1") (pintype "power_in"))
      (node (ref "U2") (pin "28") (pinfunction "GND_28") (pintype "power_in"))
      (node (ref "U2") (pin "29_1") (pinfunction "GND_29_1") (pintype "power_in"))
      (node (ref "U2") (pin "29_2") (pinfunction "GND_29_2") (pintype "power_in"))
      (node (ref "U2") (pin "29_3") (pinfunction "GND_29_3") (pintype "power_in"))
      (node (ref "U2") (pin "29_4") (pinfunction "GND_29_4") (pintype "power_in"))
      (node (ref "U2") (pin "29_5") (pinfunction "GND_29_5") (pintype "power_in"))
      (node (ref "U2") (pin "29_6") (pinfunction "GND_29_6") (pintype "power_in"))
      (node (ref "U2") (pin "29_7") (pinfunction "GND_29_7") (pintype "power_in"))
      (node (ref "U2") (pin "29_8") (pinfunction "GND_29_8") (pintype "power_in"))
      (node (ref "U2") (pin "29_9") (pinfunction "GND_29_9") (pintype "power_in"))
      (node (ref "U3") (pin "13") (pinfunction "GND_13") (pintype "power_in"))
      (node (ref "U4") (pin "1") (pinfunction "CTG_1") (pintype "power_in"))
      (node (ref "U4") (pin "4") (pinfunction "GND_4") (pintype "power_in"))
      (node (ref "U4") (pin "6") (pinfunction "QSTRT_6") (pintype "input"))
      (node (ref "U4") (pin "9") (pinfunction "EP_9") (pintype "power_in"))
    )
    (net (code "14") (name "GPIO8") (class "Default")
      (node (ref "R1") (pin "2") (pinfunction "2_2") (pintype "passive"))
      (node (ref "U2") (pin "10") (pinfunction "IO8_10") (pintype "bidirectional"))
    )
    (net (code "15") (name "I2C_PW") (class "Default")
      (node (ref "C1") (pin "1") (pinfunction "1_1") (pintype "passive"))
      (node (ref "C2") (pin "1") (pinfunction "1_1") (pintype "passive"))
      (node (ref "R1_PINH") (pin "2") (pinfunction "2_2") (pintype "passive"))
      (node (ref "R2-PINH") (pin "2") (pinfunction "2_2") (pintype "passive"))
      (node (ref "SENSOR2") (pin "2") (pinfunction "CSB_2") (pintype "input"))
      (node (ref "SENSOR2") (pin "6") (pinfunction "VDDIO_6") (pintype "power_in"))
      (node (ref "SENSOR2") (pin "8") (pinfunction "VDD_8") (pintype "power_in"))
      (node (ref "U2") (pin "17") (pinfunction "IO19_17") (pintype "bidirectional"))
    )
    (net (code "16") (name "INT_RTC") (class "Default")
      (node (ref "R1_PINH1") (pin "1") (pinfunction "1_1") (pintype "passive"))
      (node (ref "TP15") (pin "TP") (pinfunction "TP_TP") (pintype "input"))
      (node (ref "U2") (pin "8") (pinfunction "IO0_8") (pintype "bidirectional"))
      (node (ref "U3") (pin "3") (pinfunction "SQW/~{INT}_3") (pintype "output"))
    )
    (net (code "17") (name "IO{slash}BOOT") (class "Default")
      (node (ref "BOOT_BUTTON") (pin "3") (pinfunction "3_3") (pintype "passive"))
      (node (ref "BOOT_BUTTON") (pin "4") (pinfunction "4_4") (pintype "passive"))
      (node (ref "C6") (pin "1") (pinfunction "1_1") (pintype "passive"))
      (node (ref "R_BOOT") (pin "2") (pinfunction "2_2") (pintype "passive"))
      (node (ref "U2") (pin "15") (pinfunction "IO9_15") (pintype "bidirectional"))
    )
    (net (code "18") (name "IO{slash}CHANGE") (class "Default")
      (node (ref "C10") (pin "1") (pinfunction "1_1") (pintype "passive"))
      (node (ref "CHANGE_BUTTON") (pin "3") (pinfunction "3_3") (pintype "passive"))
      (node (ref "CHANGE_BUTTON") (pin "4") (pinfunction "4_4") (pintype "passive"))
      (node (ref "R_CHANGE") (pin "2") (pinfunction "2_2") (pintype "passive"))
      (node (ref "U2") (pin "23") (pinfunction "IO15_23") (pintype "bidirectional"))
    )
    (net (code "19") (name "MISO") (class "Default")
      (node (ref "D12") (pin "2") (pinfunction "2_2") (pintype "passive"))
      (node (ref "J4") (pin "P7") (pinfunction "DAT0_P7") (pintype "bidirectional"))
      (node (ref "R8") (pin "1") (pinfunction "1_1") (pintype "passive"))
      (node (ref "TP6") (pin "TP") (pinfunction "TP_TP") (pintype "input"))
      (node (ref "U1") (pin "2") (pinfunction "DO(IO1)_2") (pintype "bidirectional"))
      (node (ref "U2") (pin "27") (pinfunction "IO2_27") (pintype "bidirectional"))
    )
    (net (code "20") (name "MOSI") (class "Default")
      (node (ref "D11") (pin "2") (pinfunction "2_2") (pintype "passive"))
      (node (ref "J1") (pin "14") (pinfunction "14_14") (pintype "bidirectional"))
      (node (ref "J4") (pin "P3") (pinfunction "CMD_P3") (pintype "bidirectional"))
      (node (ref "R7") (pin "1") (pinfunction "1_1") (pintype "passive"))
      (node (ref "TP7") (pin "TP") (pinfunction "TP_TP") (pintype "input"))
      (node (ref "U1") (pin "5") (pinfunction "DI(IO0)_5") (pintype "bidirectional"))
      (node (ref "U2") (pin "7") (pinfunction "IO7_7") (pintype "bidirectional"))
    )
    (net (code "21") (name "Net-(CHG_LED-PadC)") (class "Default")
      (node (ref "CHG_LED") (pin "C") (pinfunction "C_C") (pintype "passive"))
      (node (ref "R1_BAT") (pin "2") (pinfunction "2_2") (pintype "passive"))
    )
    (net (code "22") (name "Net-(D2-CATHODE)") (class "Default")
      (node (ref "C1_BAT1") (pin "1") (pinfunction "1_1") (pintype "passive"))
      (node (ref "D2") (pin "1") (pinfunction "CATHODE_1") (pintype "bidirectional"))
      (node (ref "IC4") (pin "1") (pinfunction "VIN_1") (pintype "bidirectional"))
      (node (ref "IC4") (pin "3") (pinfunction "CE_3") (pintype "bidirectional"))
      (node (ref "Q1") (pin "2") (pinfunction "S_2") (pintype "bidirectional"))
    )
    (net (code "23") (name "Net-(D3-K)") (class "Default")
      (node (ref "C4") (pin "1") (pinfunction "1_1") (pintype "passive"))
      (node (ref "D3") (pin "1") (pinfunction "K_1") (pintype "bidirectional"))
      (node (ref "D4") (pin "2") (pinfunction "A_2") (pintype "bidirectional"))
    )
    (net (code "24") (name "Net-(D7-CATHODE)") (class "Default")
      (node (ref "D7") (pin "1") (pinfunction "CATHODE_1") (pintype "bidirectional"))
      (node (ref "R_CAPACITOR") (pin "2") (pinfunction "2_2") (pintype "passive"))
    )
    (net (code "25") (name "Net-(EPD_C1-Pad1)") (class "Default")
      (node (ref "EPD_C1") (pin "1") (pinfunction "1_1") (pintype "passive"))
      (node (ref "J1") (pin "4") (pinfunction "4_4") (pintype "bidirectional"))
    )
    (net (code "26") (name "Net-(EPD_C2-Pad1)") (class "Default")
      (node (ref "EPD_C2") (pin "1") (pinfunction "1_1") (pintype "passive"))
      (node (ref "J1") (pin "5") (pinfunction "5_5") (pintype "bidirectional"))
    )
    (net (code "27") (name "Net-(EPD_C6-Pad1)") (class "Default")
      (node (ref "EPD_C6") (pin "1") (pinfunction "1_1") (pintype "passive"))
      (node (ref "J1") (pin "18") (pinfunction "18_18") (pintype "bidirectional"))
    )
    (net (code "28") (name "Net-(EPD_C7-Pad1)") (class "Default")
      (node (ref "EPD_C7") (pin "1") (pinfunction "1_1") (pintype "passive"))
      (node (ref "J1") (pin "19") (pinfunction "19_19") (pintype "bidirectional"))
    )
    (net (code "29") (name "Net-(EPD_C8-Pad1)") (class "Default")
      (node (ref "EPD_C8") (pin "1") (pinfunction "1_1") (pintype "passive"))
      (node (ref "J1") (pin "20") (pinfunction "20_20") (pintype "bidirectional"))
    )
    (net (code "30") (name "Net-(EPD_C10-Pad1)") (class "Default")
      (node (ref "EPD_C10") (pin "1") (pinfunction "1_1") (pintype "passive"))
      (node (ref "J1") (pin "22") (pinfunction "22_22") (pintype "bidirectional"))
    )
    (net (code "31") (name "Net-(EPD_C12-Pad1)") (class "Default")
      (node (ref "EPD_C12") (pin "1") (pinfunction "1_1") (pintype "passive"))
      (node (ref "J1") (pin "24") (pinfunction "24_24") (pintype "bidirectional"))
    )
    (net (code "32") (name "Net-(IC1-CT)") (class "Default")
      (node (ref "C_DELAY") (pin "1") (pinfunction "1_1") (pintype "passive"))
      (node (ref "IC1") (pin "5") (pinfunction "CT_5") (pintype "bidirectional"))
    )
    (net (code "33") (name "Net-(J2-PadA5)") (class "Default")
      (node (ref "J2") (pin "A5") (pinfunction "A5_A5") (pintype "bidirectional"))
      (node (ref "R2-USB1") (pin "2") (pinfunction "2_2") (pintype "passive"))
    )
    (net (code "34") (name "Net-(J2-PadB5)") (class "Default")
      (node (ref "J2") (pin "B5") (pinfunction "B5_B5") (pintype "bidirectional"))
      (node (ref "R2-USB") (pin "1") (pinfunction "1_1") (pintype "passive"))
    )
    (net (code "35") (name "Net-(MCP73831-PROG)") (class "Default")
      (node (ref "MCP73831") (pin "5") (pinfunction "PROG_5") (pintype "input"))
      (node (ref "R2_BAT") (pin "2") (pinfunction "2_2") (pintype "passive"))
    )
    (net (code "36") (name "Net-(MCP73831-STAT)") (class "Default")
      (node (ref "MCP73831") (pin "1") (pinfunction "STAT_1") (pintype "output"))
      (node (ref "R1_BAT") (pin "1") (pinfunction "1_1") (pintype "passive"))
    )
    (net (code "37") (name "PREVGH") (class "Default")
      (node (ref "D5") (pin "1") (pinfunction "K_1") (pintype "bidirectional"))
      (node (ref "EPD_C9") (pin "1") (pinfunction "1_1") (pintype "passive"))
      (node (ref "J1") (pin "21") (pinfunction "21_21") (pintype "bidirectional"))
    )
    (net (code "38") (name "PREVGL") (class "Default")
      (node (ref "D3") (pin "2") (pinfunction "A_2") (pintype "bidirectional"))
      (node (ref "EPD_C11") (pin "1") (pinfunction "1_1") (pintype "passive"))
      (node (ref "J1") (pin "23") (pinfunction "23_23") (pintype "bidirectional"))
    )
    (net (code "39") (name "RESE") (class "Default")
      (node (ref "J1") (pin "3") (pinfunction "3_3") (pintype "bidirectional"))
      (node (ref "Q3") (pin "2") (pinfunction "S_2") (pintype "bidirectional"))
      (node (ref "R3") (pin "1") (pinfunction "1_1") (pintype "passive"))
    )
    (net (code "40") (name "RESE'") (class "Default")
      (node (ref "R2") (pin "2") (pinfunction "2_2") (pintype "passive"))
      (node (ref "R3") (pin "2") (pinfunction "2_2") (pintype "passive"))
      (node (ref "SJ1") (pin "2") (pinfunction "2_2") (pintype "passive"))
    )
    (net (code "41") (name "RESET") (class "Default")
      (node (ref "C5") (pin "1") (pinfunction "1_1") (pintype "passive"))
      (node (ref "IC1") (pin "1") (pinfunction "VOUT_1") (pintype "bidirectional"))
      (node (ref "RESET_BUTTON") (pin "3") (pinfunction "3_3") (pintype "passive"))
      (node (ref "RESET_BUTTON") (pin "4") (pinfunction "4_4") (pintype "passive"))
      (node (ref "R_RESET") (pin "2") (pinfunction "2_2") (pintype "passive"))
      (node (ref "U2") (pin "3") (pinfunction "EN_3") (pintype "input"))
    )
    (net (code "42") (name "RTC_RST") (class "Default")
      (node (ref "U2") (pin "16") (pinfunction "IO18_16") (pintype "bidirectional"))
      (node (ref "U3") (pin "4") (pinfunction "~{RST}_4") (pintype "input"))
    )
    (net (code "43") (name "RX") (class "Default")
      (node (ref "TP2") (pin "TP") (pinfunction "TP_TP") (pintype "input"))
      (node (ref "U2") (pin "24") (pinfunction "RXD0/GPIO17_24") (pintype "bidirectional"))
    )
    (net (code "44") (name "SCK") (class "Default")
      (node (ref "D10") (pin "2") (pinfunction "2_2") (pintype "passive"))
      (node (ref "J1") (pin "13") (pinfunction "13_13") (pintype "bidirectional"))
      (node (ref "J4") (pin "P5") (pinfunction "CLK_P5") (pintype "bidirectional"))
      (node (ref "R6") (pin "1") (pinfunction "1_1") (pintype "passive"))
      (node (ref "TP8") (pin "TP") (pinfunction "TP_TP") (pintype "input"))
      (node (ref "U1") (pin "6") (pinfunction "CLK_6") (pintype "input"))
      (node (ref "U2") (pin "6") (pinfunction "IO6_6") (pintype "bidirectional"))
    )
    (net (code "45") (name "SCL") (class "Default")
      (node (ref "J3") (pin "4") (pinfunction "4_4") (pintype "passive"))
      (node (ref "R2-PINH") (pin "1") (pinfunction "1_1") (pintype "passive"))
      (node (ref "SENSOR2") (pin "4") (pinfunction "SCK_4") (pintype "input"))
      (node (ref "U2") (pin "20") (pinfunction "IO22_20") (pintype "bidirectional"))
      (node (ref "U3") (pin "16") (pinfunction "SCL_16") (pintype "input"))
      (node (ref "U4") (pin "7") (pinfunction "SCL_7") (pintype "input"))
    )
    (net (code "46") (name "SDA") (class "Default")
      (node (ref "J3") (pin "3") (pinfunction "3_3") (pintype "passive"))
      (node (ref "R1_PINH") (pin "1") (pinfunction "1_1") (pintype "passive"))
      (node (ref "SENSOR2") (pin "3") (pinfunction "SDI_3") (pintype "bidirectional"))
      (node (ref "U2") (pin "19") (pinfunction "IO21_19") (pintype "bidirectional"))
      (node (ref "U3") (pin "15") (pinfunction "SDA_15") (pintype "bidirectional"))
      (node (ref "U4") (pin "8") (pinfunction "SDA_8") (pintype "bidirectional"))
    )
    (net (code "47") (name "SRC") (class "Default")
      (node (ref "C4") (pin "2") (pinfunction "2_2") (pintype "passive"))
      (node (ref "D5") (pin "2") (pinfunction "A_2") (pintype "bidirectional"))
      (node (ref "L1") (pin "1") (pinfunction "1_1") (pintype "passive"))
      (node (ref "Q3") (pin "3") (pinfunction "D_3") (pintype "bidirectional"))
    )
    (net (code "48") (name "SS_SD") (class "Default")
      (node (ref "D8") (pin "2") (pinfunction "2_2") (pintype "passive"))
      (node (ref "J4") (pin "P2") (pinfunction "CD/DAT3_P2") (pintype "bidirectional"))
      (node (ref "R10") (pin "1") (pinfunction "1_1") (pintype "passive"))
      (node (ref "U2") (pin "4") (pinfunction "IO4_4") (pintype "bidirectional"))
    )
    (net (code "49") (name "TX") (class "Default")
      (node (ref "TP1") (pin "TP") (pinfunction "TP_TP") (pintype "input"))
      (node (ref "U2") (pin "25") (pinfunction "TXD0/GPIO16_25") (pintype "bidirectional"))
    )
    (net (code "50") (name "USB_D+") (class "Default")
      (node (ref "D1") (pin "1") (pinfunction "I/O1_1_1") (pintype "bidirectional"))
      (node (ref "U2") (pin "14") (pinfunction "IO13_14") (pintype "bidirectional"))
    )
    (net (code "51") (name "USB_D-") (class "Default")
      (node (ref "D1") (pin "3") (pinfunction "I/O2_1_3") (pintype "bidirectional"))
      (node (ref "U2") (pin "13") (pinfunction "IO12_13") (pintype "bidirectional"))
    )
    (net (code "52") (name "VBAT") (class "Default")
      (node (ref "C2_BAT") (pin "1") (pinfunction "1_1") (pintype "passive"))
      (node (ref "MCP73831") (pin "3") (pinfunction "VBAT_3") (pintype "power_in"))
      (node (ref "Q1") (pin "3") (pinfunction "D_3") (pintype "bidirectional"))
      (node (ref "TP3") (pin "TP") (pinfunction "TP_TP") (pintype "input"))
      (node (ref "U4") (pin "2") (pinfunction "CELL_2") (pintype "power_in"))
      (node (ref "U4") (pin "3") (pinfunction "VDD_3") (pintype "power_in"))
    )
    (net (code "53") (name "VBUS") (class "Default")
      (node (ref "C1_BAT") (pin "1") (pinfunction "1_1") (pintype "passive"))
      (node (ref "C4_USB") (pin "1") (pinfunction "1_1") (pintype "passive"))
      (node (ref "C5_USB") (pin "1") (pinfunction "1_1") (pintype "passive"))
      (node (ref "CHG_LED") (pin "A") (pinfunction "A_A") (pintype "passive"))
      (node (ref "D1") (pin "5") (pinfunction "VBUS_5") (pintype "bidirectional"))
      (node (ref "D2") (pin "2") (pinfunction "ANODE_2") (pintype "bidirectional"))
      (node (ref "MCP73831") (pin "4") (pinfunction "VIN_4") (pintype "power_in"))
      (node (ref "PFMF.050.1") (pin "2") (pinfunction "2_2") (pintype "passive"))
      (node (ref "Q1") (pin "1") (pinfunction "G_1") (pintype "bidirectional"))
      (node (ref "R1_PWRUSB") (pin "2") (pinfunction "2_2") (pintype "passive"))
      (node (ref "TP14") (pin "TP") (pinfunction "TP_TP") (pintype "input"))
    )
    (net (code "54") (name "VRTC") (class "Default")
      (node (ref "C10_SUPERCAP") (pin "2") (pinfunction "2_2") (pintype "passive"))
      (node (ref "C8") (pin "1") (pinfunction "1_1") (pintype "passive"))
      (node (ref "R_CAPACITOR") (pin "1") (pinfunction "1_1") (pintype "passive"))
      (node (ref "U3") (pin "14") (pinfunction "VBAT_14") (pintype "power_in"))
    )
    (net (code "55") (name "VUSB") (class "Default")
      (node (ref "J2") (pin "A4") (pinfunction "A4_A4") (pintype "bidirectional"))
      (node (ref "J2") (pin "A9") (pinfunction "A9_A9") (pintype "bidirectional"))
      (node (ref "J2") (pin "B4") (pinfunction "B4_B4") (pintype "bidirectional"))
      (node (ref "J2") (pin "B9") (pinfunction "B9_B9") (pintype "bidirectional"))
      (node (ref "PFMF.050.1") (pin "1") (pinfunction "1_1") (pintype "passive"))
    )
    (net (code "56") (name "unconnected-(IC1-NC-Pad4)") (class "Default")
      (node (ref "IC1") (pin "4") (pinfunction "NC_4") (pintype "no_connect"))
    )
    (net (code "57") (name "unconnected-(IC4-NC-Pad4)") (class "Default")
      (node (ref "IC4") (pin "4") (pinfunction "NC_4") (pintype "no_connect"))
    )
    (net (code "58") (name "unconnected-(J1-Pad1)") (class "Default")
      (node (ref "J1") (pin "1") (pinfunction "1_1") (pintype "bidirectional"))
    )
    (net (code "59") (name "unconnected-(J1-Pad6)") (class "Default")
      (node (ref "J1") (pin "6") (pinfunction "6_6") (pintype "bidirectional"))
    )
    (net (code "60") (name "unconnected-(J1-Pad7)") (class "Default")
      (node (ref "J1") (pin "7") (pinfunction "7_7") (pintype "bidirectional"))
    )
    (net (code "61") (name "unconnected-(J2-PadA8)") (class "Default")
      (node (ref "J2") (pin "A8") (pinfunction "A8_A8") (pintype "bidirectional"))
    )
    (net (code "62") (name "unconnected-(J2-PadB8)") (class "Default")
      (node (ref "J2") (pin "B8") (pinfunction "B8_B8") (pintype "bidirectional"))
    )
    (net (code "63") (name "unconnected-(J4-DAT1-PadP8)") (class "Default")
      (node (ref "J4") (pin "P8") (pinfunction "DAT1_P8") (pintype "bidirectional"))
    )
    (net (code "64") (name "unconnected-(J4-DAT2-PadP1)") (class "Default")
      (node (ref "J4") (pin "P1") (pinfunction "DAT2_P1") (pintype "bidirectional"))
    )
    (net (code "65") (name "unconnected-(J4-DETECTION_1-PadS1)") (class "Default")
      (node (ref "J4") (pin "S1") (pinfunction "DETECTION_1_S1") (pintype "bidirectional"))
    )
    (net (code "66") (name "unconnected-(J4-DETECTION_2-PadS2)") (class "Default")
      (node (ref "J4") (pin "S2") (pinfunction "DETECTION_2_S2") (pintype "bidirectional"))
    )
    (net (code "67") (name "unconnected-(U2-NC-Pad22)") (class "Default")
      (node (ref "U2") (pin "22") (pinfunction "NC_22") (pintype "no_connect"))
    )
    (net (code "68") (name "unconnected-(U4-~{ALERT}-Pad5)") (class "Default")
      (node (ref "U4") (pin "5") (pinfunction "~{ALERT}_5") (pintype "output"))
    )
  )
)
